# HIVE_SIGHT_USB.net
KiCad netlist of a schematic drawn in Altium Designer
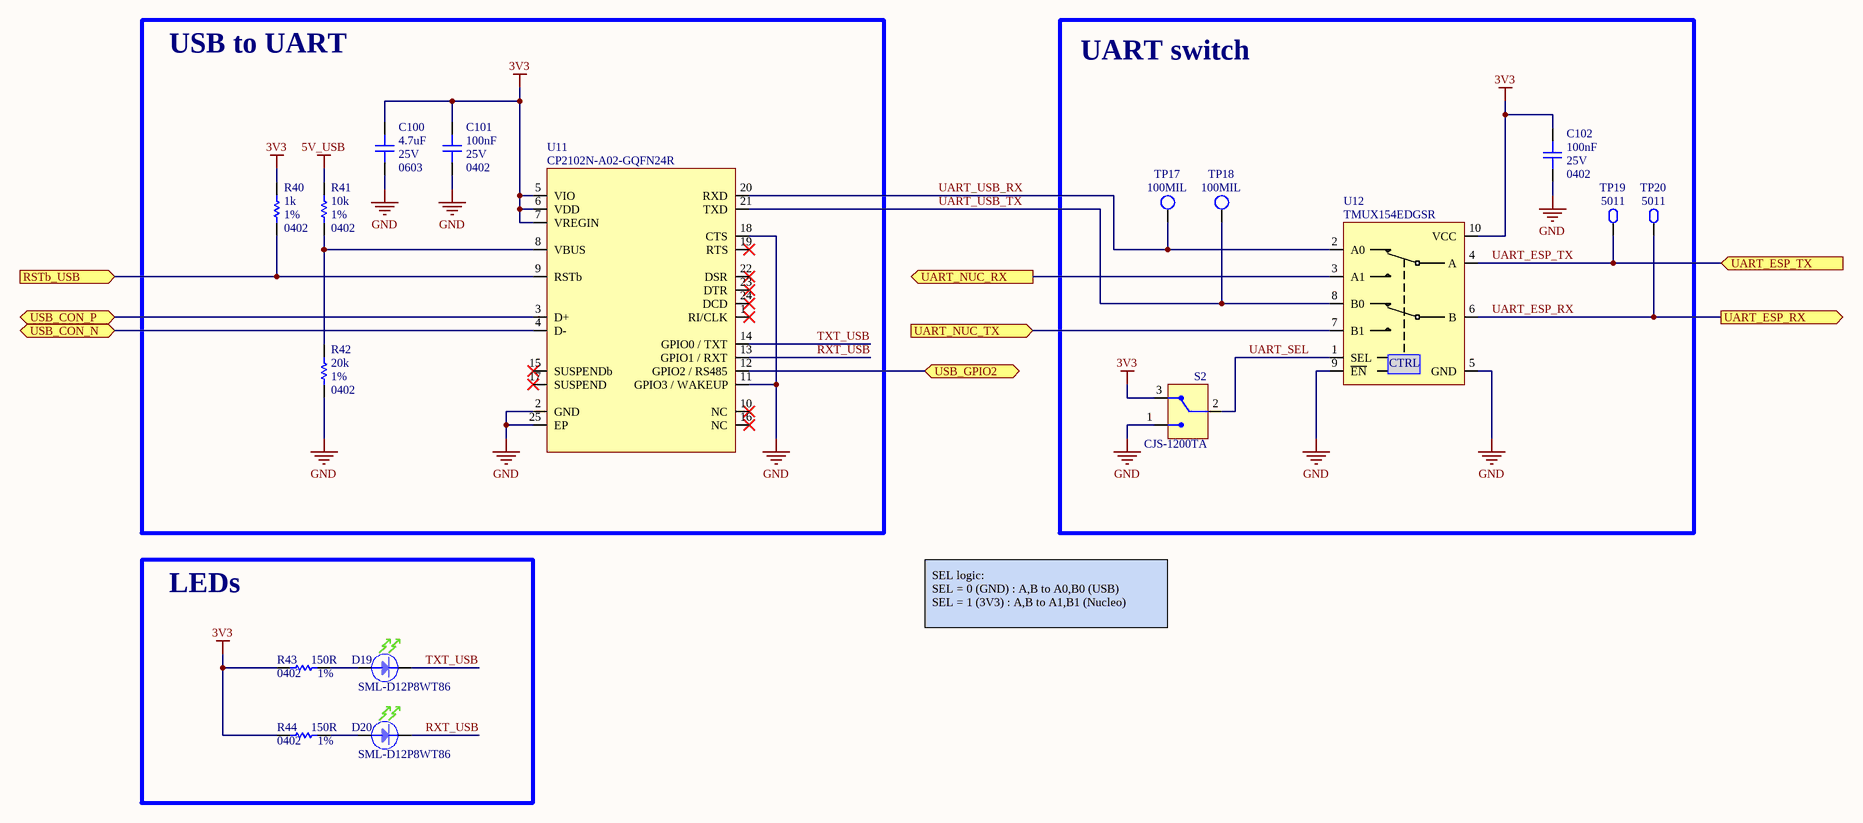
[diagram p0: HIVE_SIGHT_USB.SchDoc]

(export (version "E")
  (design (tool "Eeschema 10.0.6"))
  (components
    (comp (ref "C100")
      (value "4.7uF")
      (footprint "CAP_CER_0603")
      (description "CAP - CER 4.7µF 20% 25V X5R - 0603")
      (fields
        (field (name "TOLERANCE") "20%")
        (field (name "PACKAGE") "0603")
        (field (name "VOLTAGE RATING") "25V")
        (field (name "Comment") "CL10A475MA8NQNC")
        (field (name "CREATEDBY/DATE") "Nicolas Roy 2018-11-21")
        (field (name "VERIFIEDBY") "Nicolas V. (2019-01-22)")
      )
      (libsource (lib "GRAMS_MASTER_LIB") (part "CAP_CER_CL10A475MA8NQNC"))
    )
    (comp (ref "C101")
      (value "100nF")
      (footprint "CAP_CER_0402")
      (description "CAP - CER 0.1µF 10% 25V X7R - 0402")
      (fields
        (field (name "TOLERANCE") "10%")
        (field (name "PACKAGE") "0402")
        (field (name "VOLTAGE RATING") "25V")
        (field (name "Comment") "CGA2B3X7R1E104K050BB")
        (field (name "CREATEDBY/DATE") "Nicolas Roy 2018-11-07")
        (field (name "VERIFIEDBY") "Nicolas V. (2019-01-22)")
      )
      (libsource (lib "GRAMS_MASTER_LIB") (part "CAP_CER_CGA2B3X7R1E104K050BB"))
    )
    (comp (ref "C102")
      (value "100nF")
      (footprint "GRAMS_MASTER_LIB_PCB:CAP_CER_0402")
      (description "CAP - CER 0.1µF 10% 25V X7R - 0402")
      (fields
        (field (name "TOLERANCE") "10%")
        (field (name "PACKAGE") "0402")
        (field (name "VOLTAGE RATING") "25V")
        (field (name "Comment") "CGA2B3X7R1E104K050BB")
        (field (name "CREATEDBY/DATE") "Nicolas Roy 2018-11-07")
        (field (name "VERIFIEDBY") "Nicolas V. (2019-01-22)")
      )
      (libsource (lib "GRAMS_MASTER_LIB_SCH") (part "CAP_CER_CGA2B3X7R1E104K050BB"))
    )
    (comp (ref "D19")
      (value "SML-D12P8WT86")
      (footprint "GRAMS_MASTER_LIB_PCB:LED_SML-D12P8WT86")
      (description "LED - GREEN DIFFUSED 0603 SMD - 0603")
      (fields
        (field (name "CREATEDBY/DATE") "Keven Deslandes - 2018/11/21")
        (field (name "VERIFIEDBY") "Caroline Paulin - 13 février 2019")
      )
      (libsource (lib "GRAMS_MASTER_LIB_SCH") (part "LED_SML-D12P8WT86"))
    )
    (comp (ref "D20")
      (value "SML-D12P8WT86")
      (footprint "GRAMS_MASTER_LIB_PCB:LED_SML-D12P8WT86")
      (description "LED - GREEN DIFFUSED 0603 SMD - 0603")
      (fields
        (field (name "CREATEDBY/DATE") "Keven Deslandes - 2018/11/21")
        (field (name "VERIFIEDBY") "Caroline Paulin - 13 février 2019")
      )
      (libsource (lib "GRAMS_MASTER_LIB_SCH") (part "LED_SML-D12P8WT86"))
    )
    (comp (ref "R40")
      (value "1k")
      (footprint "RES_0402")
      (description "RES - 1K OHM 1% 1/16W - 0402")
      (fields
        (field (name "TOLERANCE") "1%")
        (field (name "PACKAGE") "0402")
        (field (name "Comment") "RC0402FR-071KL")
        (field (name "CREATEDBY/DATE") "Jonathan Bouchard 2018-07-05")
        (field (name "VERIFIEDBY") "Arnaud Samson 16-07-18")
      )
      (libsource (lib "GRAMS_MASTER_LIB") (part "RES_RC0402FR-071KL"))
    )
    (comp (ref "R41")
      (value "10k")
      (footprint "GRAMS_MASTER_LIB_PCB:RES_0402")
      (description "RES - 10K OHMS 1% 1/16W - 0402")
      (fields
        (field (name "TOLERANCE") "1%")
        (field (name "PACKAGE") "0402")
        (field (name "Comment") "RC0402FR-0710KL")
        (field (name "CREATEDBY/DATE") "Nicolas V. (2018-11-20)")
        (field (name "VERIFIEDBY") "Nicolas V. (2018-11-20)")
      )
      (libsource (lib "GRAMS_MASTER_LIB_SCH") (part "RES_RC0402FR-0710KL"))
    )
    (comp (ref "R42")
      (value "20k")
      (footprint "GRAMS_MASTER_LIB_PCB:RES_0402")
      (description "RES - 20K 1% 1/16W  - 0402")
      (fields
        (field (name "TOLERANCE") "1%")
        (field (name "PACKAGE") "0402")
        (field (name "Comment") "RC0402FR-0720KL")
        (field (name "CREATEDBY/DATE") "Keven Deslandes 2018-10-18")
        (field (name "VERIFIEDBY") "Caroline Paulin - 7 janv 2019")
      )
      (libsource (lib "GRAMS_MASTER_LIB_SCH") (part "RES_RC0402FR-0720KL"))
    )
    (comp (ref "R43")
      (value "150R")
      (footprint "RES_0402")
      (description "RES - 150R 1% 1/16W - 0402")
      (fields
        (field (name "TOLERANCE") "1%")
        (field (name "PACKAGE") "0402")
        (field (name "Comment") "RC0402FR-07150RL")
        (field (name "CREATEDBY/DATE") "Jonathan Bouchard 2019-03-25")
        (field (name "VERIFIEDBY") "Nicolas V. (2019-05-02)")
      )
      (libsource (lib "GRAMS_MASTER_LIB") (part "RES_RC0402FR-07150RL"))
    )
    (comp (ref "R44")
      (value "150R")
      (footprint "RES_0402")
      (description "RES - 150R 1% 1/16W - 0402")
      (fields
        (field (name "TOLERANCE") "1%")
        (field (name "PACKAGE") "0402")
        (field (name "Comment") "RC0402FR-07150RL")
        (field (name "CREATEDBY/DATE") "Jonathan Bouchard 2019-03-25")
        (field (name "VERIFIEDBY") "Nicolas V. (2019-05-02)")
      )
      (libsource (lib "GRAMS_MASTER_LIB") (part "RES_RC0402FR-07150RL"))
    )
    (comp (ref "S2")
      (value "CJS-1200TA")
      (footprint "SWI_SPDT_CJS-1200TA")
      (description "SWI - SLIDE SPDT 100MA 6V - SMD")
      (fields
        (field (name "CREATEDBY/DATE") "Caroline Paulin - 15/11/2018")
        (field (name "VERIFIEDBY") "Nicolas V. (2018-11-16)")
      )
      (libsource (lib "GRAMS_MASTER_LIB") (part "SWI_SPDT_CJS-1200TA"))
    )
    (comp (ref "TP17")
      (value "100MIL")
      (footprint "grams_master_lib_pcb:TPO_TH_ROUND_100MIL")
      (description "TPO - TEST POINT ROUND TH  - 100MIL")
      (fields
        (field (name "CREATEDBY/DATE") "Louis-Daniel Gaulin/ 14/01/2020")
        (field (name "VERIFIEDBY") "C.Paulin - 21/01/2020")
      )
      (libsource (lib "GRAMS_MASTER_LIB_SCH") (part "TPO_TH_ROUND_100MIL"))
    )
    (comp (ref "TP18")
      (value "100MIL")
      (footprint "grams_master_lib_pcb:TPO_TH_ROUND_100MIL")
      (description "TPO - TEST POINT ROUND TH  - 100MIL")
      (fields
        (field (name "CREATEDBY/DATE") "Louis-Daniel Gaulin/ 14/01/2020")
        (field (name "VERIFIEDBY") "C.Paulin - 21/01/2020")
      )
      (libsource (lib "GRAMS_MASTER_LIB_SCH") (part "TPO_TH_ROUND_100MIL"))
    )
    (comp (ref "TP19")
      (value "5011")
      (footprint "TPO_5011")
      (description "TPO - TEST POINT - TH")
      (fields
        (field (name "CREATEDBY/DATE") "Louis-Daniel Gauli / 02-11-2020")
        (field (name "VERIFIEDBY") "Philippe Arsenault/2020-11-06")
      )
      (libsource (lib "SWARMUS_LIB") (part "TPO_5011"))
    )
    (comp (ref "TP20")
      (value "5011")
      (footprint "TPO_5011")
      (description "TPO - TEST POINT - TH")
      (fields
        (field (name "CREATEDBY/DATE") "Louis-Daniel Gauli / 02-11-2020")
        (field (name "VERIFIEDBY") "Philippe Arsenault/2020-11-06")
      )
      (libsource (lib "SWARMUS_LIB") (part "TPO_5011"))
    )
    (comp (ref "U11")
      (value "CP2102N-A02-GQFN24R")
      (footprint "COM_XCV_CP2102N-A02-GQFN24R")
      (description "COM_XCV - IC USB TO UART BRIDGE - 24-QFN (4x4)")
      (fields
        (field (name "CREATEDBY/DATE") "Louis-Daniel Gaulin / 06-10-2020")
        (field (name "VERIFIEDBY") "Philippe Arsenault/2020-11-06")
      )
      (libsource (lib "SWARMUS_LIB") (part "COM_XCV_CP2102N-A02-GQFN24R"))
    )
    (comp (ref "U12")
      (value "TMUX154EDGSR")
      (footprint "LOG_MUX_TMUX154EDGSR")
      (description "LOG_MUX -  SWITCH SPDT DUAL 2:1 - 10-VSSOP")
      (fields
        (field (name "CREATEDBY/DATE") "Louis-Daniel Gaulin / 06-10-2020")
        (field (name "VERIFIEDBY") "Philippe Arsenault/2020-11-06")
      )
      (libsource (lib "SWARMUS_LIB") (part "LOG_MUX_TMUX154EDGSR"))
    )
  )
  (nets
    (net (code "1") (name "/RSTb_USB") (class "Default")
      (node (ref "R40") (pin "2") (pinfunction "2_2") (pintype "passive"))
      (node (ref "U11") (pin "9") (pinfunction "RSTb_9") (pintype "passive"))
    )
    (net (code "2") (name "/RXT_USB") (class "Default")
      (node (ref "D20") (pin "K") (pinfunction "K_K") (pintype "passive"))
      (node (ref "U11") (pin "13") (pinfunction "GPIO1_/_RXT_13") (pintype "passive"))
    )
    (net (code "3") (name "/TXT_USB") (class "Default")
      (node (ref "D19") (pin "K") (pinfunction "K_K") (pintype "passive"))
      (node (ref "U11") (pin "14") (pinfunction "GPIO0_/_TXT_14") (pintype "passive"))
    )
    (net (code "4") (name "/UART_ESP_RX") (class "Default")
      (node (ref "TP20") (pin "1") (pinfunction "1_1") (pintype "passive"))
      (node (ref "U12") (pin "6") (pinfunction "B_6") (pintype "passive"))
    )
    (net (code "5") (name "/UART_ESP_TX") (class "Default")
      (node (ref "TP19") (pin "1") (pinfunction "1_1") (pintype "passive"))
      (node (ref "U12") (pin "4") (pinfunction "A_4") (pintype "passive"))
    )
    (net (code "6") (name "/UART_NUC_RX") (class "Default")
      (node (ref "U12") (pin "3") (pinfunction "A1_3") (pintype "passive"))
    )
    (net (code "7") (name "/UART_NUC_TX") (class "Default")
      (node (ref "U12") (pin "7") (pinfunction "B1_7") (pintype "passive"))
    )
    (net (code "8") (name "/UART_SEL") (class "Default")
      (node (ref "S2") (pin "2") (pinfunction "2_2") (pintype "passive"))
      (node (ref "U12") (pin "1") (pinfunction "SEL_1") (pintype "passive"))
    )
    (net (code "9") (name "/UART_USB_RX") (class "Default")
      (node (ref "TP17") (pin "1") (pinfunction "1_1") (pintype "passive"))
      (node (ref "U11") (pin "20") (pinfunction "RXD_20") (pintype "passive"))
      (node (ref "U12") (pin "2") (pinfunction "A0_2") (pintype "passive"))
    )
    (net (code "10") (name "/UART_USB_TX") (class "Default")
      (node (ref "TP18") (pin "1") (pinfunction "1_1") (pintype "passive"))
      (node (ref "U11") (pin "21") (pinfunction "TXD_21") (pintype "passive"))
      (node (ref "U12") (pin "8") (pinfunction "B0_8") (pintype "passive"))
    )
    (net (code "11") (name "/USB_CON_N") (class "Default")
      (node (ref "U11") (pin "4") (pinfunction "D-_4") (pintype "passive"))
    )
    (net (code "12") (name "/USB_CON_P") (class "Default")
      (node (ref "U11") (pin "3") (pinfunction "D+_3") (pintype "passive"))
    )
    (net (code "13") (name "/USB_GPIO2") (class "Default")
      (node (ref "U11") (pin "12") (pinfunction "GPIO2_/_RS485_12") (pintype "passive"))
    )
    (net (code "14") (name "3V3") (class "Default")
      (node (ref "C100") (pin "2") (pinfunction "2_2") (pintype "passive"))
      (node (ref "C101") (pin "2") (pinfunction "2_2") (pintype "passive"))
      (node (ref "C102") (pin "1") (pinfunction "1_1") (pintype "passive"))
      (node (ref "R40") (pin "1") (pinfunction "1_1") (pintype "passive"))
      (node (ref "R43") (pin "1") (pinfunction "1_1") (pintype "passive"))
      (node (ref "R44") (pin "1") (pinfunction "1_1") (pintype "passive"))
      (node (ref "S2") (pin "3") (pinfunction "3_3") (pintype "passive"))
      (node (ref "U11") (pin "5") (pinfunction "VIO_5") (pintype "passive"))
      (node (ref "U11") (pin "6") (pinfunction "VDD_6") (pintype "passive"))
      (node (ref "U11") (pin "7") (pinfunction "VREGIN_7") (pintype "passive"))
      (node (ref "U12") (pin "10") (pinfunction "VCC_10") (pintype "passive"))
    )
    (net (code "15") (name "5V_USB") (class "Default")
      (node (ref "R41") (pin "2") (pinfunction "2_2") (pintype "passive"))
    )
    (net (code "16") (name "GND") (class "Default")
      (node (ref "C100") (pin "1") (pinfunction "1_1") (pintype "passive"))
      (node (ref "C101") (pin "1") (pinfunction "1_1") (pintype "passive"))
      (node (ref "C102") (pin "2") (pinfunction "2_2") (pintype "passive"))
      (node (ref "R42") (pin "1") (pinfunction "1_1") (pintype "passive"))
      (node (ref "S2") (pin "1") (pinfunction "1_1") (pintype "passive"))
      (node (ref "U11") (pin "11") (pinfunction "GPIO3_/_WAKEUP_11") (pintype "passive"))
      (node (ref "U11") (pin "18") (pinfunction "CTS_18") (pintype "passive"))
      (node (ref "U11") (pin "2") (pinfunction "GND_2") (pintype "passive"))
      (node (ref "U11") (pin "25") (pinfunction "EP_25") (pintype "passive"))
      (node (ref "U12") (pin "5") (pinfunction "GND_5") (pintype "passive"))
      (node (ref "U12") (pin "9") (pinfunction "EN_9") (pintype "passive"))
    )
    (net (code "17") (name "Net-(D19-PadA)") (class "Default")
      (node (ref "D19") (pin "A") (pinfunction "A_A") (pintype "passive"))
      (node (ref "R43") (pin "2") (pinfunction "2_2") (pintype "passive"))
    )
    (net (code "18") (name "Net-(D20-PadA)") (class "Default")
      (node (ref "D20") (pin "A") (pinfunction "A_A") (pintype "passive"))
      (node (ref "R44") (pin "2") (pinfunction "2_2") (pintype "passive"))
    )
    (net (code "19") (name "Net-(U11-VBUS)") (class "Default")
      (node (ref "R41") (pin "1") (pinfunction "1_1") (pintype "passive"))
      (node (ref "R42") (pin "2") (pinfunction "2_2") (pintype "passive"))
      (node (ref "U11") (pin "8") (pinfunction "VBUS_8") (pintype "passive"))
    )
    (net (code "20") (name "unconnected-(U11-DCD-Pad24)") (class "Default")
      (node (ref "U11") (pin "24") (pinfunction "DCD_24") (pintype "passive+no_connect"))
    )
    (net (code "21") (name "unconnected-(U11-DSR-Pad22)") (class "Default")
      (node (ref "U11") (pin "22") (pinfunction "DSR_22") (pintype "passive+no_connect"))
    )
    (net (code "22") (name "unconnected-(U11-DTR-Pad23)") (class "Default")
      (node (ref "U11") (pin "23") (pinfunction "DTR_23") (pintype "passive+no_connect"))
    )
    (net (code "23") (name "unconnected-(U11-NC-Pad10)") (class "Default")
      (node (ref "U11") (pin "10") (pinfunction "NC_10") (pintype "passive+no_connect"))
    )
    (net (code "24") (name "unconnected-(U11-NC-Pad16)") (class "Default")
      (node (ref "U11") (pin "16") (pinfunction "NC_16") (pintype "passive+no_connect"))
    )
    (net (code "25") (name "unconnected-(U11-RI{slash}CLK-Pad1)") (class "Default")
      (node (ref "U11") (pin "1") (pinfunction "RI/CLK_1") (pintype "passive+no_connect"))
    )
    (net (code "26") (name "unconnected-(U11-RTS-Pad19)") (class "Default")
      (node (ref "U11") (pin "19") (pinfunction "RTS_19") (pintype "passive+no_connect"))
    )
    (net (code "27") (name "unconnected-(U11-SUSPEND-Pad17)") (class "Default")
      (node (ref "U11") (pin "17") (pinfunction "SUSPEND_17") (pintype "passive+no_connect"))
    )
    (net (code "28") (name "unconnected-(U11-SUSPENDb-Pad15)") (class "Default")
      (node (ref "U11") (pin "15") (pinfunction "SUSPENDb_15") (pintype "passive+no_connect"))
    )
  )
)
